# 5V_XL4016_Buck_Converter_2023_05_04_A.net
KiCad netlist of a schematic drawn in EAGLE
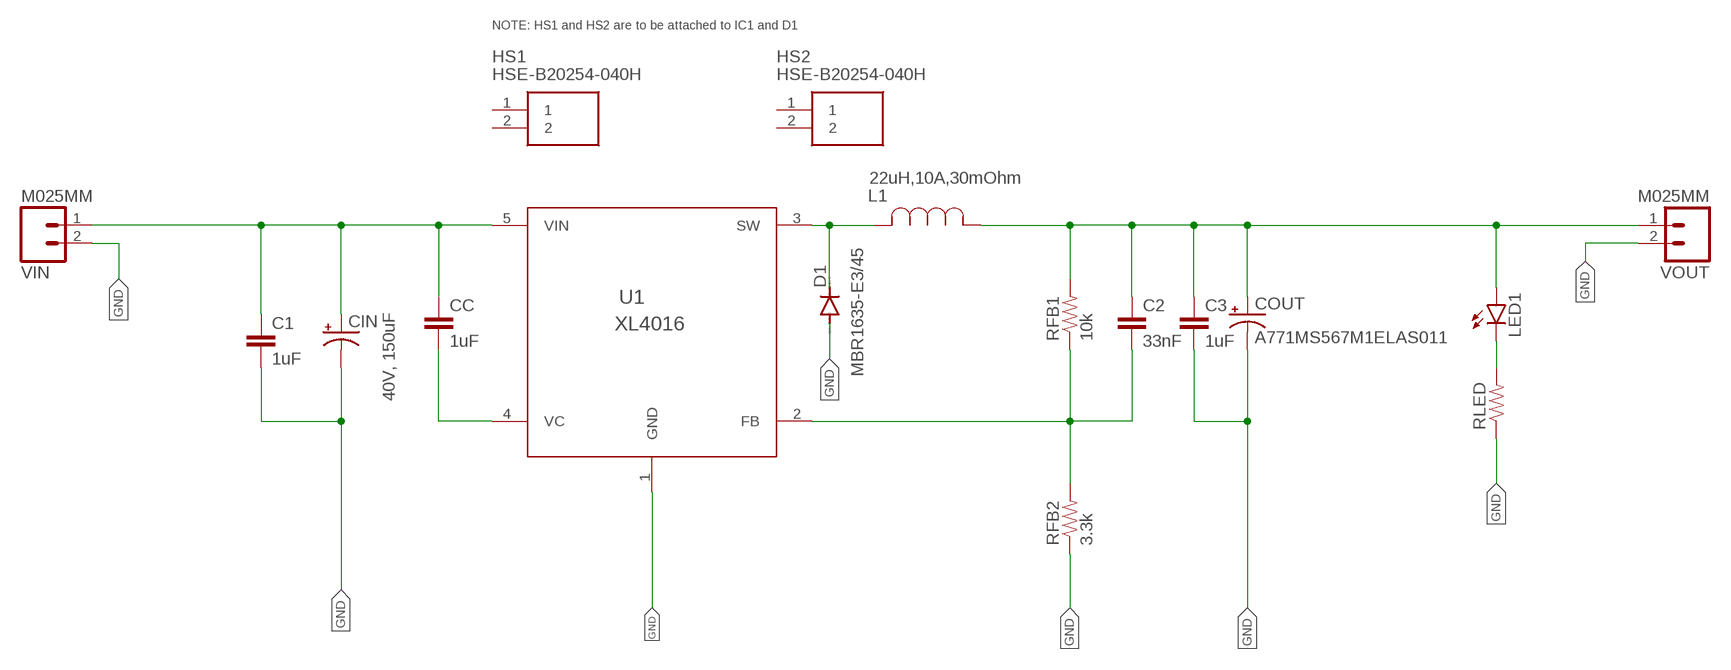
[diagram p0: schematic, sheet 1]

(export (version "E")
  (design (tool "Eeschema 10.0.6"))
  (components
    (comp (ref "C1")
      (value "1uF")
      (footprint "eagle-import:0805")
      (libsource (lib "eagle-import") (part "CAP0805"))
    )
    (comp (ref "C2")
      (value "33nF")
      (footprint "eagle-import:0805")
      (libsource (lib "eagle-import") (part "CAP0805"))
    )
    (comp (ref "C3")
      (value "1uF")
      (footprint "eagle-import:0805")
      (libsource (lib "eagle-import") (part "CAP0805"))
    )
    (comp (ref "CC")
      (value "1uF")
      (footprint "eagle-import:0805")
      (libsource (lib "eagle-import") (part "CAP0805"))
    )
    (comp (ref "CIN")
      (value "40V, 150uF")
      (footprint "eagle-import:CAP_A768_KEM-M")
      (fields
        (field (name "MANUFACTURER_PART_NUMBER") "A768KS157M1GLAS025")
        (field (name "COPYRIGHT") "Copyright (C) 2023 Ultra Librarian. All rights reserved.")
      )
      (libsource (lib "eagle-import") (part "A768KS157M1GLAS025CAP_A768_KEM-M"))
    )
    (comp (ref "COUT")
      (value "A771MS567M1ELAS011")
      (footprint "eagle-import:153CLV-1012")
      (libsource (lib "eagle-import") (part "CPOL-US153CLV-1012"))
    )
    (comp (ref "D1")
      (value "MBR1635-E3/45")
      (footprint "eagle-import:DO220S")
      (libsource (lib "eagle-import") (part "FES08AT"))
    )
    (comp (ref "HS1")
      (value "HSE-B20254-040H")
      (footprint "eagle-import:HSEB20254040H")
      (fields (field (name "MOUSER_PART_NUMBER") "490-HSE-B20254-040H"))
      (libsource (lib "eagle-import") (part "HSE-B20254-040H"))
    )
    (comp (ref "HS2")
      (value "HSE-B20254-040H")
      (footprint "eagle-import:HSEB20254040H")
      (fields (field (name "MOUSER_PART_NUMBER") "490-HSE-B20254-040H"))
      (libsource (lib "eagle-import") (part "HSE-B20254-040H"))
    )
    (comp (ref "L1")
      (value "22uH,10A,30mOhm")
      (footprint "eagle-import:IND_SRP1265C-LEADFRAME_BRN-M")
      (fields
        (field (name "MANUFACTURER_PART_NUMBER") "SRP1265C-4R7M")
        (field (name "COPYRIGHT") "Copyright (C) 2023 Ultra Librarian. All rights reserved.")
      )
      (libsource (lib "eagle-import") (part "SRP1265C-4R7MIND_SRP1265C-LEADFRAME_BRN-M"))
    )
    (comp (ref "LED1")
      (value "LED1206")
      (footprint "eagle-import:LED-1206")
      (libsource (lib "eagle-import") (part "LED1206"))
    )
    (comp (ref "RFB1")
      (value "10k")
      (footprint "eagle-import:0805")
      (libsource (lib "eagle-import") (part "RESISTOR0805-RES"))
    )
    (comp (ref "RFB2")
      (value "3.3k")
      (footprint "eagle-import:0805")
      (libsource (lib "eagle-import") (part "RESISTOR0805-RES"))
    )
    (comp (ref "RLED")
      (value "RESISTOR0805-RES")
      (footprint "eagle-import:0805")
      (libsource (lib "eagle-import") (part "RESISTOR0805-RES"))
    )
    (comp (ref "U1")
      (value "XL4016")
      (footprint "eagle-import:TO220-5L")
      (fields
        (field (name "MANUFACTURER_PART_NUMBER") "LM2575T-12/NOPB")
        (field (name "COPYRIGHT") "Copyright (C) 2023 Ultra Librarian. All rights reserved.")
      )
      (libsource (lib "eagle-import") (part "XL4016"))
    )
    (comp (ref "VIN")
      (value "M025MM")
      (footprint "eagle-import:SCREWTERMINAL-5MM-2")
      (libsource (lib "eagle-import") (part "M025MM"))
    )
    (comp (ref "VOUT")
      (value "M025MM")
      (footprint "eagle-import:SCREWTERMINAL-5MM-2")
      (libsource (lib "eagle-import") (part "M025MM"))
    )
  )
  (nets
    (net (code "1") (name "GND") (class "Default")
      (node (ref "C1") (pin "2") (pinfunction "2_2") (pintype "passive"))
      (node (ref "C3") (pin "2") (pinfunction "2_2") (pintype "passive"))
      (node (ref "CIN") (pin "2") (pinfunction "-_2") (pintype "passive"))
      (node (ref "COUT") (pin "-") (pinfunction "-_-") (pintype "passive"))
      (node (ref "D1") (pin "A") (pinfunction "A_A") (pintype "passive"))
      (node (ref "RFB2") (pin "1") (pinfunction "1_1") (pintype "passive"))
      (node (ref "RLED") (pin "1") (pinfunction "1_1") (pintype "passive"))
      (node (ref "U1") (pin "1") (pinfunction "GND_1") (pintype "power_in"))
      (node (ref "VIN") (pin "2") (pinfunction "2_2") (pintype "passive"))
      (node (ref "VOUT") (pin "2") (pinfunction "2_2") (pintype "passive"))
    )
    (net (code "2") (name "Net-(C2-Pad1)") (class "Default")
      (node (ref "C2") (pin "1") (pinfunction "1_1") (pintype "passive"))
      (node (ref "C3") (pin "1") (pinfunction "1_1") (pintype "passive"))
      (node (ref "COUT") (pin "+") (pinfunction "+_+") (pintype "passive"))
      (node (ref "L1") (pin "1") (pinfunction "1_1") (pintype "passive"))
      (node (ref "LED1") (pin "A") (pinfunction "A_A") (pintype "passive"))
      (node (ref "RFB1") (pin "2") (pinfunction "2_2") (pintype "passive"))
      (node (ref "VOUT") (pin "1") (pinfunction "1_1") (pintype "passive"))
    )
    (net (code "3") (name "Net-(CIN-+)") (class "Default")
      (node (ref "C1") (pin "1") (pinfunction "1_1") (pintype "passive"))
      (node (ref "CC") (pin "1") (pinfunction "1_1") (pintype "passive"))
      (node (ref "CIN") (pin "1") (pinfunction "+_1") (pintype "passive"))
      (node (ref "U1") (pin "5") (pinfunction "VIN_5") (pintype "power_in"))
      (node (ref "VIN") (pin "1") (pinfunction "1_1") (pintype "passive"))
    )
    (net (code "4") (name "Net-(LED1-PadC)") (class "Default")
      (node (ref "LED1") (pin "C") (pinfunction "C_C") (pintype "passive"))
      (node (ref "RLED") (pin "2") (pinfunction "2_2") (pintype "passive"))
    )
    (net (code "5") (name "Net-(U1-FB)") (class "Default")
      (node (ref "C2") (pin "2") (pinfunction "2_2") (pintype "passive"))
      (node (ref "RFB1") (pin "1") (pinfunction "1_1") (pintype "passive"))
      (node (ref "RFB2") (pin "2") (pinfunction "2_2") (pintype "passive"))
      (node (ref "U1") (pin "2") (pinfunction "FB_2") (pintype "input"))
    )
    (net (code "6") (name "Net-(U1-SW)") (class "Default")
      (node (ref "D1") (pin "C") (pinfunction "C_C") (pintype "passive"))
      (node (ref "L1") (pin "2") (pinfunction "2_2") (pintype "passive"))
      (node (ref "U1") (pin "3") (pinfunction "SW_3") (pintype "output"))
    )
    (net (code "7") (name "Net-(U1-VC)") (class "Default")
      (node (ref "CC") (pin "2") (pinfunction "2_2") (pintype "passive"))
      (node (ref "U1") (pin "4") (pinfunction "VC_4") (pintype "input"))
    )
    (net (code "8") (name "unconnected-(HS1-Pad1)") (class "Default")
      (node (ref "HS1") (pin "1") (pinfunction "1_1") (pintype "bidirectional"))
    )
    (net (code "9") (name "unconnected-(HS1-Pad2)") (class "Default")
      (node (ref "HS1") (pin "2") (pinfunction "2_2") (pintype "bidirectional"))
    )
    (net (code "10") (name "unconnected-(HS2-Pad1)") (class "Default")
      (node (ref "HS2") (pin "1") (pinfunction "1_1") (pintype "bidirectional"))
    )
    (net (code "11") (name "unconnected-(HS2-Pad2)") (class "Default")
      (node (ref "HS2") (pin "2") (pinfunction "2_2") (pintype "bidirectional"))
    )
  )
)
